# NNP-DWG-165-001-000_BP2_Modular_and_TGes.net
KiCad netlist of a schematic drawn in Altium Designer
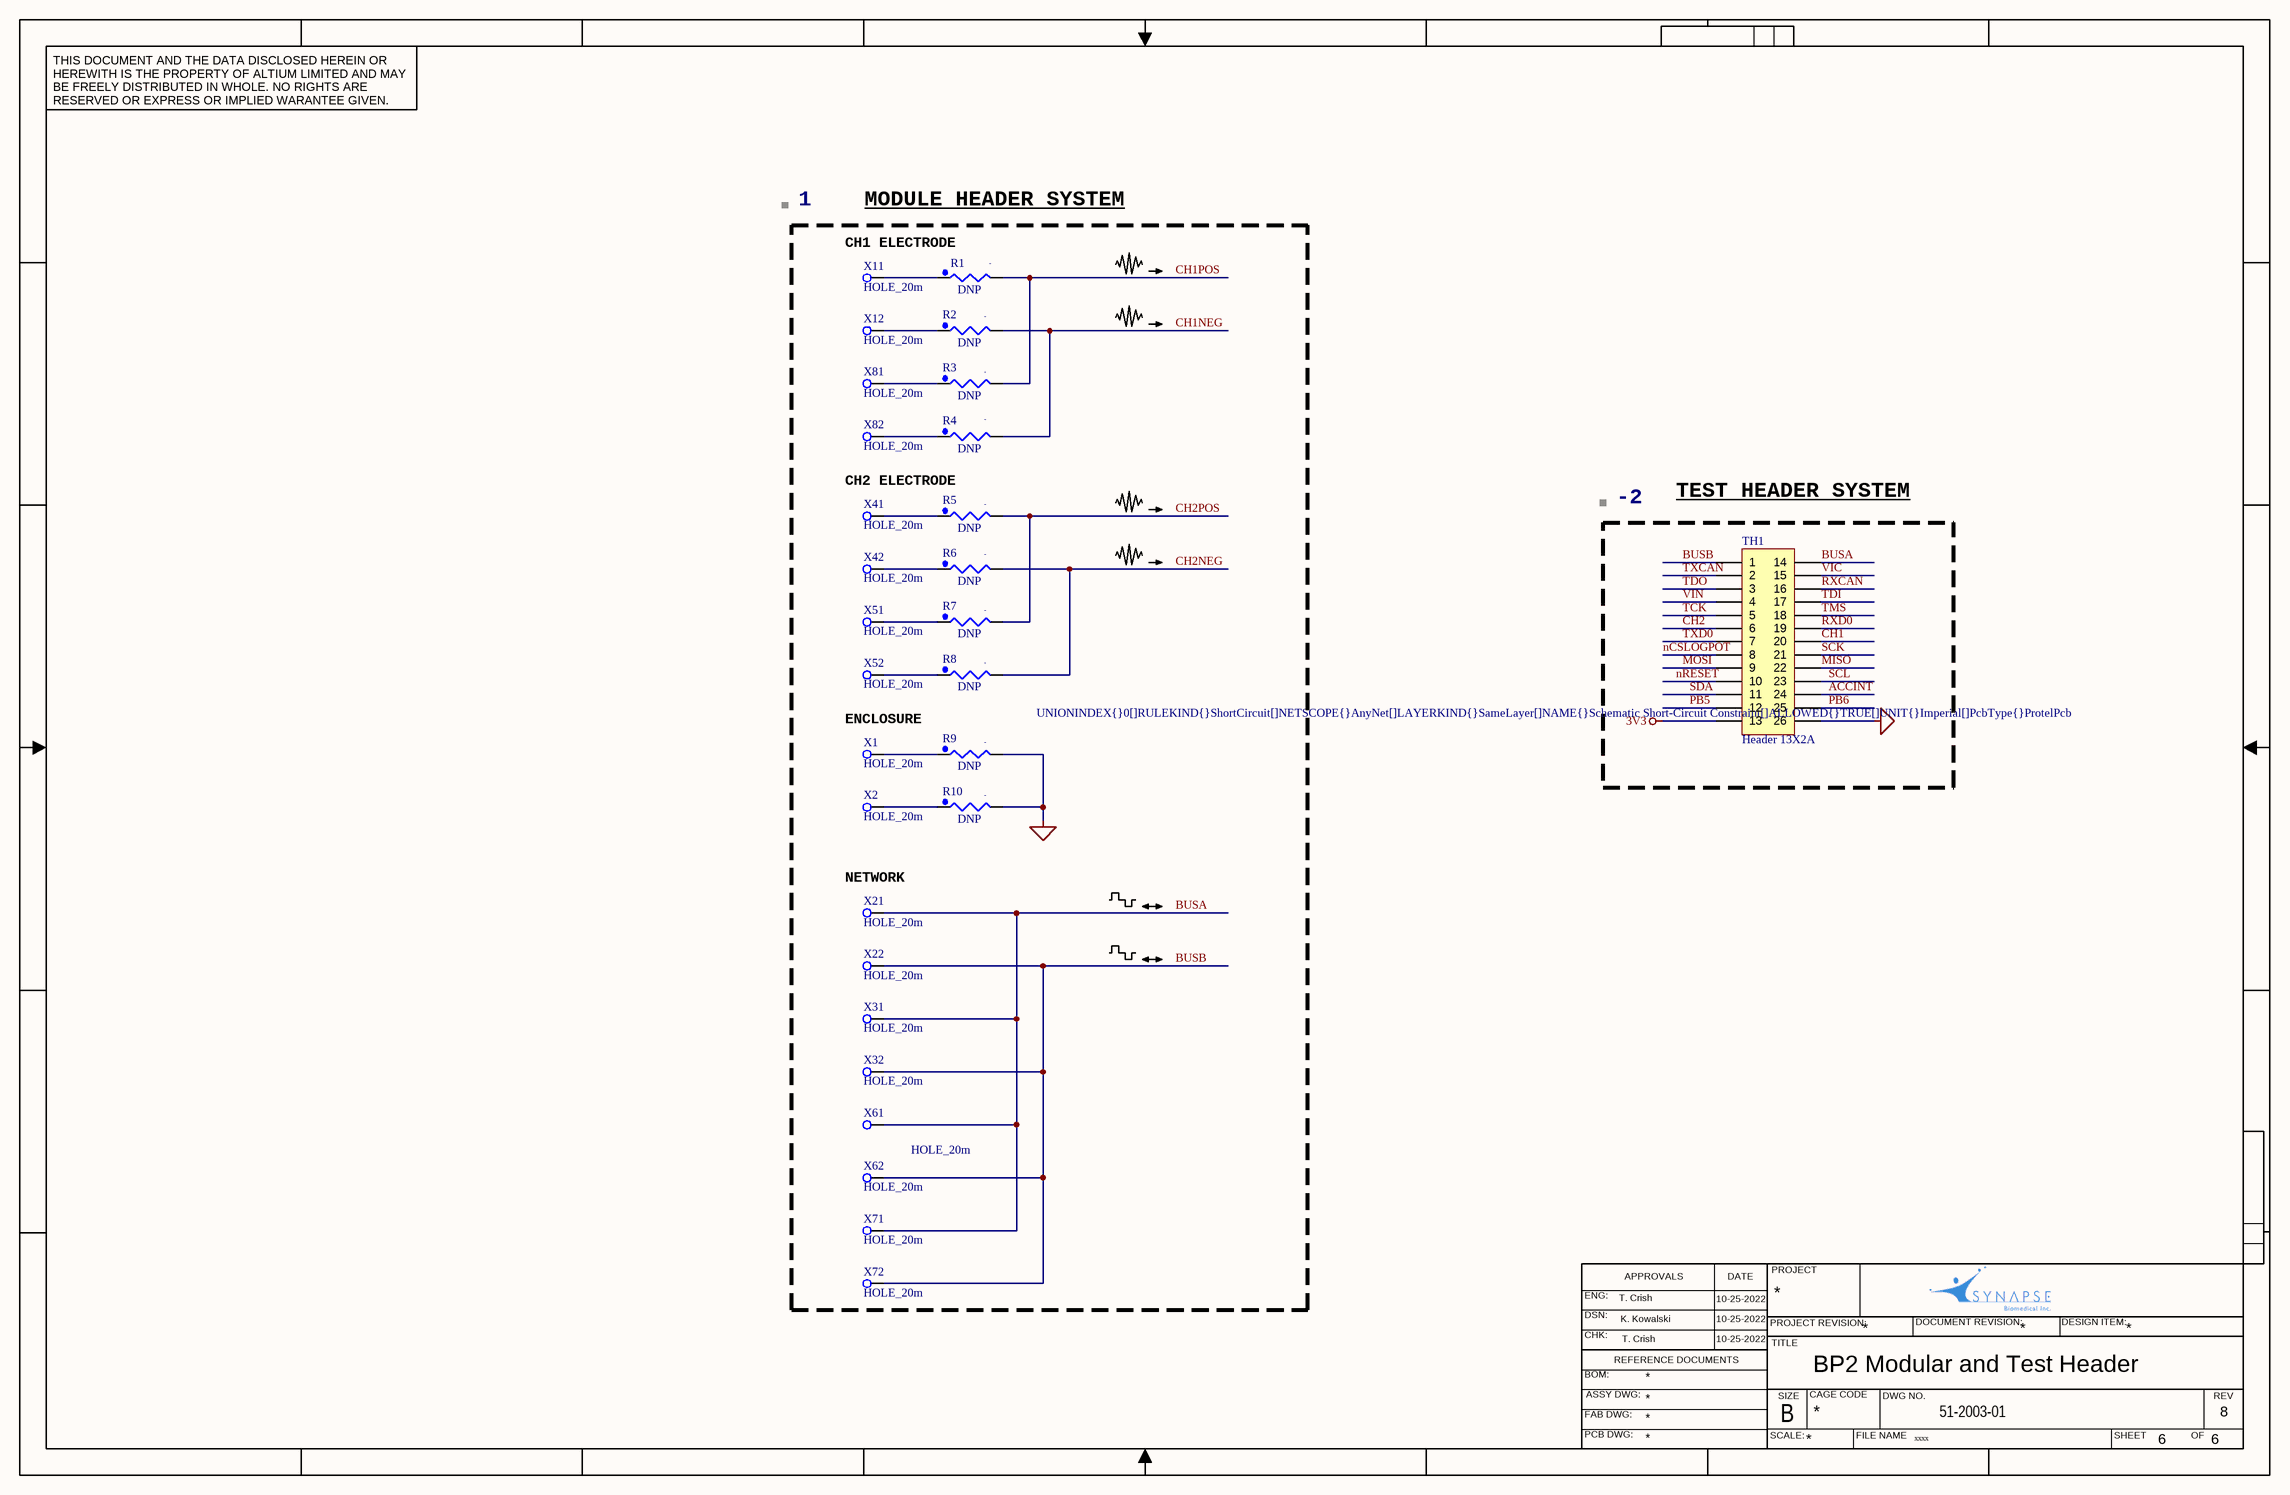
[diagram p0: NNP-DWG-165-001-000 BP2 Modular and TGest Header Pg 6 of 6.SchDoc]

(export (version "E")
  (design (tool "Eeschema 10.0.6"))
  (components
    (comp (ref "-2")
      (value "BOM_S1")
      (description "BOM item small graphic")
      (fields (field (name "XDESCRIPTION") "TEST HEADER SYSTEM"))
      (libsource (lib "BOM_sym") (part "BOM_S1"))
    )
    (comp (ref "1")
      (value "BOM_S1")
      (description "BOM item small graphic")
      (fields (field (name "XDESCRIPTION") "MODULE HEADER SYSTEM"))
      (libsource (lib "BOM_sym") (part "BOM_S1"))
    )
    (comp (ref "R1")
      (value "DNP")
      (footprint "52-2002_1:RES_0402_cut")
      (description "0.0 ohm, 1/16W, 0402, RoHS")
      (fields (field (name "PACKAGEDESCRIPTION") "-"))
      (libsource (lib "NNPS Integrated Parts") (part "-"))
    )
    (comp (ref "R2")
      (value "DNP")
      (footprint "RES_0402_cut")
      (description "0.0 ohm, 1/16W, 0402, RoHS")
      (fields (field (name "PACKAGEDESCRIPTION") "-"))
      (libsource (lib "NNPS Integrated Parts") (part "-"))
    )
    (comp (ref "R3")
      (value "DNP")
      (footprint "RES_0402_cut")
      (description "0.0 ohm, 1/16W, 0402, RoHS")
      (fields
        (field (name "PACKAGEDESCRIPTION") "-")
        (field (name "RULE") "UNIONINDEX{}0[]RULEKIND{}ShortCircuit[]NETSCOPE{}AnyNet[]LAYERKIND{}SameLayer[]NAME{}Schematic Short-Circuit Constraint[]ALLOWED{}TRUE[]UNIT{}Imperial[]PcbType{}ProtelPcb")
      )
      (libsource (lib "NNPS Integrated Parts") (part "-"))
    )
    (comp (ref "R4")
      (value "DNP")
      (footprint "RES_0402_cut")
      (description "0.0 ohm, 1/16W, 0402, RoHS")
      (fields (field (name "PACKAGEDESCRIPTION") "-"))
      (libsource (lib "NNPS Integrated Parts") (part "-"))
    )
    (comp (ref "R5")
      (value "DNP")
      (footprint "RES_0402_cut")
      (description "0.0 ohm, 1/16W, 0402, RoHS")
      (fields (field (name "PACKAGEDESCRIPTION") "-"))
      (libsource (lib "NNPS Integrated Parts") (part "-"))
    )
    (comp (ref "R6")
      (value "DNP")
      (footprint "RES_0402_cut")
      (description "0.0 ohm, 1/16W, 0402, RoHS")
      (fields (field (name "PACKAGEDESCRIPTION") "-"))
      (libsource (lib "NNPS Integrated Parts") (part "-"))
    )
    (comp (ref "R7")
      (value "DNP")
      (footprint "RES_0402_cut")
      (description "0.0 ohm, 1/16W, 0402, RoHS")
      (fields (field (name "PACKAGEDESCRIPTION") "-"))
      (libsource (lib "NNPS Integrated Parts") (part "-"))
    )
    (comp (ref "R8")
      (value "DNP")
      (footprint "RES_0402_cut")
      (description "0.0 ohm, 1/16W, 0402, RoHS")
      (fields (field (name "PACKAGEDESCRIPTION") "-"))
      (libsource (lib "NNPS Integrated Parts") (part "-"))
    )
    (comp (ref "R9")
      (value "DNP")
      (footprint "RES_0402_cut")
      (description "0.0 ohm, 1/16W, 0402, RoHS")
      (fields (field (name "PACKAGEDESCRIPTION") "-"))
      (libsource (lib "NNPS Integrated Parts") (part "-"))
    )
    (comp (ref "R10")
      (value "DNP")
      (footprint "RES_0402_cut")
      (description "0.0 ohm, 1/16W, 0402, RoHS")
      (fields (field (name "PACKAGEDESCRIPTION") "-"))
      (libsource (lib "NNPS Integrated Parts") (part "-"))
    )
    (comp (ref "TH1")
      (value "Header 13X2A")
      (footprint "HDR2X13_CEN")
      (description "Header, 13-Pin, Dual row")
      (fields (field (name "PUBLISHER") "Altium Limited"))
      (libsource (lib "Miscellaneous Connectors") (part "Header 13X2A"))
    )
    (comp (ref "X1")
      (value "HOLE_20m")
      (footprint "FEEDHOLE_20mil")
      (description "Hole for 10mil diameter feedthrough")
      (libsource (lib "NNPS Integrated Parts") (part "HOLE_20m"))
    )
    (comp (ref "X2")
      (value "HOLE_20m")
      (footprint "FEEDHOLE_20mil")
      (description "Hole for 10mil diameter feedthrough")
      (libsource (lib "NNPS Integrated Parts") (part "HOLE_20m"))
    )
    (comp (ref "X11")
      (value "HOLE_20m")
      (footprint "FEEDHOLE_20mil")
      (description "Hole for 10mil diameter feedthrough")
      (libsource (lib "NNPS Integrated Parts") (part "HOLE_20m"))
    )
    (comp (ref "X12")
      (value "HOLE_20m")
      (footprint "FEEDHOLE_20mil")
      (description "Hole for 10mil diameter feedthrough")
      (libsource (lib "NNPS Integrated Parts") (part "HOLE_20m"))
    )
    (comp (ref "X21")
      (value "HOLE_20m")
      (footprint "FEEDHOLE_20mil")
      (description "Hole for 10mil diameter feedthrough")
      (libsource (lib "NNPS Integrated Parts") (part "HOLE_20m"))
    )
    (comp (ref "X22")
      (value "HOLE_20m")
      (footprint "FEEDHOLE_20mil")
      (description "Hole for 10mil diameter feedthrough")
      (libsource (lib "NNPS Integrated Parts") (part "HOLE_20m"))
    )
    (comp (ref "X31")
      (value "HOLE_20m")
      (footprint "FEEDHOLE_20mil")
      (description "Hole for 10mil diameter feedthrough")
      (libsource (lib "NNPS Integrated Parts") (part "HOLE_20m"))
    )
    (comp (ref "X32")
      (value "HOLE_20m")
      (footprint "FEEDHOLE_20mil")
      (description "Hole for 10mil diameter feedthrough")
      (libsource (lib "NNPS Integrated Parts") (part "HOLE_20m"))
    )
    (comp (ref "X41")
      (value "HOLE_20m")
      (footprint "FEEDHOLE_20mil")
      (description "Hole for 10mil diameter feedthrough")
      (libsource (lib "NNPS Integrated Parts") (part "HOLE_20m"))
    )
    (comp (ref "X42")
      (value "HOLE_20m")
      (footprint "FEEDHOLE_20mil")
      (description "Hole for 10mil diameter feedthrough")
      (libsource (lib "NNPS Integrated Parts") (part "HOLE_20m"))
    )
    (comp (ref "X51")
      (value "HOLE_20m")
      (footprint "FEEDHOLE_20mil")
      (description "Hole for 10mil diameter feedthrough")
      (libsource (lib "NNPS Integrated Parts") (part "HOLE_20m"))
    )
    (comp (ref "X52")
      (value "HOLE_20m")
      (footprint "FEEDHOLE_20mil")
      (description "Hole for 10mil diameter feedthrough")
      (libsource (lib "NNPS Integrated Parts") (part "HOLE_20m"))
    )
    (comp (ref "X61")
      (value "HOLE_20m")
      (footprint "FEEDHOLE_20mil")
      (description "Hole for 10mil diameter feedthrough")
      (libsource (lib "NNPS Integrated Parts") (part "HOLE_20m"))
    )
    (comp (ref "X62")
      (value "HOLE_20m")
      (footprint "FEEDHOLE_20mil")
      (description "Hole for 10mil diameter feedthrough")
      (libsource (lib "NNPS Integrated Parts") (part "HOLE_20m"))
    )
    (comp (ref "X71")
      (value "HOLE_20m")
      (footprint "FEEDHOLE_20mil")
      (description "Hole for 10mil diameter feedthrough")
      (libsource (lib "NNPS Integrated Parts") (part "HOLE_20m"))
    )
    (comp (ref "X72")
      (value "HOLE_20m")
      (footprint "FEEDHOLE_20mil")
      (description "Hole for 10mil diameter feedthrough")
      (libsource (lib "NNPS Integrated Parts") (part "HOLE_20m"))
    )
    (comp (ref "X81")
      (value "HOLE_20m")
      (footprint "FEEDHOLE_20mil")
      (description "Hole for 10mil diameter feedthrough")
      (libsource (lib "NNPS Integrated Parts") (part "HOLE_20m"))
    )
    (comp (ref "X82")
      (value "HOLE_20m")
      (footprint "FEEDHOLE_20mil")
      (description "Hole for 10mil diameter feedthrough")
      (libsource (lib "NNPS Integrated Parts") (part "HOLE_20m"))
    )
  )
  (nets
    (net (code "1") (name "/ACCINT") (class "Default")
      (node (ref "TH1") (pin "24") (pinfunction "24_24") (pintype "passive"))
    )
    (net (code "2") (name "/BUSA") (class "Default")
      (node (ref "TH1") (pin "14") (pinfunction "14_14") (pintype "passive"))
      (node (ref "X21") (pin "1") (pinfunction "1_1") (pintype "passive"))
      (node (ref "X31") (pin "1") (pinfunction "1_1") (pintype "passive"))
      (node (ref "X61") (pin "1") (pinfunction "1_1") (pintype "passive"))
      (node (ref "X71") (pin "1") (pinfunction "1_1") (pintype "passive"))
    )
    (net (code "3") (name "/BUSB") (class "Default")
      (node (ref "TH1") (pin "1") (pinfunction "1_1") (pintype "passive"))
      (node (ref "X22") (pin "1") (pinfunction "1_1") (pintype "passive"))
      (node (ref "X32") (pin "1") (pinfunction "1_1") (pintype "passive"))
      (node (ref "X62") (pin "1") (pinfunction "1_1") (pintype "passive"))
      (node (ref "X72") (pin "1") (pinfunction "1_1") (pintype "passive"))
    )
    (net (code "4") (name "/CH1") (class "Default")
      (node (ref "TH1") (pin "20") (pinfunction "20_20") (pintype "passive"))
    )
    (net (code "5") (name "/CH1NEG") (class "Default")
      (node (ref "R2") (pin "2") (pinfunction "2_2") (pintype "passive"))
      (node (ref "R4") (pin "2") (pinfunction "2_2") (pintype "passive"))
    )
    (net (code "6") (name "/CH1POS") (class "Default")
      (node (ref "R1") (pin "2") (pinfunction "2_2") (pintype "passive"))
      (node (ref "R3") (pin "2") (pinfunction "2_2") (pintype "passive"))
    )
    (net (code "7") (name "/CH2") (class "Default")
      (node (ref "TH1") (pin "6") (pinfunction "6_6") (pintype "passive"))
    )
    (net (code "8") (name "/CH2NEG") (class "Default")
      (node (ref "R6") (pin "2") (pinfunction "2_2") (pintype "passive"))
      (node (ref "R8") (pin "2") (pinfunction "2_2") (pintype "passive"))
    )
    (net (code "9") (name "/CH2POS") (class "Default")
      (node (ref "R5") (pin "2") (pinfunction "2_2") (pintype "passive"))
      (node (ref "R7") (pin "2") (pinfunction "2_2") (pintype "passive"))
    )
    (net (code "10") (name "/MISO") (class "Default")
      (node (ref "TH1") (pin "22") (pinfunction "22_22") (pintype "passive"))
    )
    (net (code "11") (name "/MOSI") (class "Default")
      (node (ref "TH1") (pin "9") (pinfunction "9_9") (pintype "passive"))
    )
    (net (code "12") (name "/PB5") (class "Default")
      (node (ref "TH1") (pin "12") (pinfunction "12_12") (pintype "passive"))
    )
    (net (code "13") (name "/PB6") (class "Default")
      (node (ref "TH1") (pin "25") (pinfunction "25_25") (pintype "passive"))
    )
    (net (code "14") (name "/RXCAN") (class "Default")
      (node (ref "TH1") (pin "16") (pinfunction "16_16") (pintype "passive"))
    )
    (net (code "15") (name "/RXD0") (class "Default")
      (node (ref "TH1") (pin "19") (pinfunction "19_19") (pintype "passive"))
    )
    (net (code "16") (name "/SCK") (class "Default")
      (node (ref "TH1") (pin "21") (pinfunction "21_21") (pintype "passive"))
    )
    (net (code "17") (name "/SCL") (class "Default")
      (node (ref "TH1") (pin "23") (pinfunction "23_23") (pintype "passive"))
    )
    (net (code "18") (name "/SDA") (class "Default")
      (node (ref "TH1") (pin "11") (pinfunction "11_11") (pintype "passive"))
    )
    (net (code "19") (name "/TCK") (class "Default")
      (node (ref "TH1") (pin "5") (pinfunction "5_5") (pintype "passive"))
    )
    (net (code "20") (name "/TDI") (class "Default")
      (node (ref "TH1") (pin "17") (pinfunction "17_17") (pintype "passive"))
    )
    (net (code "21") (name "/TDO") (class "Default")
      (node (ref "TH1") (pin "3") (pinfunction "3_3") (pintype "passive"))
    )
    (net (code "22") (name "/TMS") (class "Default")
      (node (ref "TH1") (pin "18") (pinfunction "18_18") (pintype "passive"))
    )
    (net (code "23") (name "/TXCAN") (class "Default")
      (node (ref "TH1") (pin "2") (pinfunction "2_2") (pintype "passive"))
    )
    (net (code "24") (name "/TXD0") (class "Default")
      (node (ref "TH1") (pin "7") (pinfunction "7_7") (pintype "passive"))
    )
    (net (code "25") (name "/VIC") (class "Default")
      (node (ref "TH1") (pin "15") (pinfunction "15_15") (pintype "passive"))
    )
    (net (code "26") (name "/VIN") (class "Default")
      (node (ref "TH1") (pin "4") (pinfunction "4_4") (pintype "passive"))
    )
    (net (code "27") (name "/nCSLOGPOT") (class "Default")
      (node (ref "TH1") (pin "8") (pinfunction "8_8") (pintype "passive"))
    )
    (net (code "28") (name "/nRESET") (class "Default")
      (node (ref "TH1") (pin "10") (pinfunction "10_10") (pintype "passive"))
    )
    (net (code "29") (name "3V3") (class "Default")
      (node (ref "TH1") (pin "13") (pinfunction "13_13") (pintype "passive"))
    )
    (net (code "30") (name "GND") (class "Default")
      (node (ref "R10") (pin "2") (pinfunction "2_2") (pintype "passive"))
      (node (ref "R9") (pin "2") (pinfunction "2_2") (pintype "passive"))
      (node (ref "TH1") (pin "26") (pinfunction "26_26") (pintype "passive"))
    )
    (net (code "31") (name "Net-(R1-Pad1)") (class "Default")
      (node (ref "R1") (pin "1") (pinfunction "1_1") (pintype "passive"))
      (node (ref "X11") (pin "1") (pinfunction "1_1") (pintype "passive"))
    )
    (net (code "32") (name "Net-(R2-Pad1)") (class "Default")
      (node (ref "R2") (pin "1") (pinfunction "1_1") (pintype "passive"))
      (node (ref "X12") (pin "1") (pinfunction "1_1") (pintype "passive"))
    )
    (net (code "33") (name "Net-(R3-Pad1)") (class "Default")
      (node (ref "R3") (pin "1") (pinfunction "1_1") (pintype "passive"))
      (node (ref "X81") (pin "1") (pinfunction "1_1") (pintype "passive"))
    )
    (net (code "34") (name "Net-(R4-Pad1)") (class "Default")
      (node (ref "R4") (pin "1") (pinfunction "1_1") (pintype "passive"))
      (node (ref "X82") (pin "1") (pinfunction "1_1") (pintype "passive"))
    )
    (net (code "35") (name "Net-(R5-Pad1)") (class "Default")
      (node (ref "R5") (pin "1") (pinfunction "1_1") (pintype "passive"))
      (node (ref "X41") (pin "1") (pinfunction "1_1") (pintype "passive"))
    )
    (net (code "36") (name "Net-(R6-Pad1)") (class "Default")
      (node (ref "R6") (pin "1") (pinfunction "1_1") (pintype "passive"))
      (node (ref "X42") (pin "1") (pinfunction "1_1") (pintype "passive"))
    )
    (net (code "37") (name "Net-(R7-Pad1)") (class "Default")
      (node (ref "R7") (pin "1") (pinfunction "1_1") (pintype "passive"))
      (node (ref "X51") (pin "1") (pinfunction "1_1") (pintype "passive"))
    )
    (net (code "38") (name "Net-(R8-Pad1)") (class "Default")
      (node (ref "R8") (pin "1") (pinfunction "1_1") (pintype "passive"))
      (node (ref "X52") (pin "1") (pinfunction "1_1") (pintype "passive"))
    )
    (net (code "39") (name "Net-(R9-Pad1)") (class "Default")
      (node (ref "R9") (pin "1") (pinfunction "1_1") (pintype "passive"))
      (node (ref "X1") (pin "1") (pinfunction "1_1") (pintype "passive"))
    )
    (net (code "40") (name "Net-(R10-Pad1)") (class "Default")
      (node (ref "R10") (pin "1") (pinfunction "1_1") (pintype "passive"))
      (node (ref "X2") (pin "1") (pinfunction "1_1") (pintype "passive"))
    )
  )
)
